# BANK500_501.net
KiCad netlist of a schematic drawn in Altium Designer
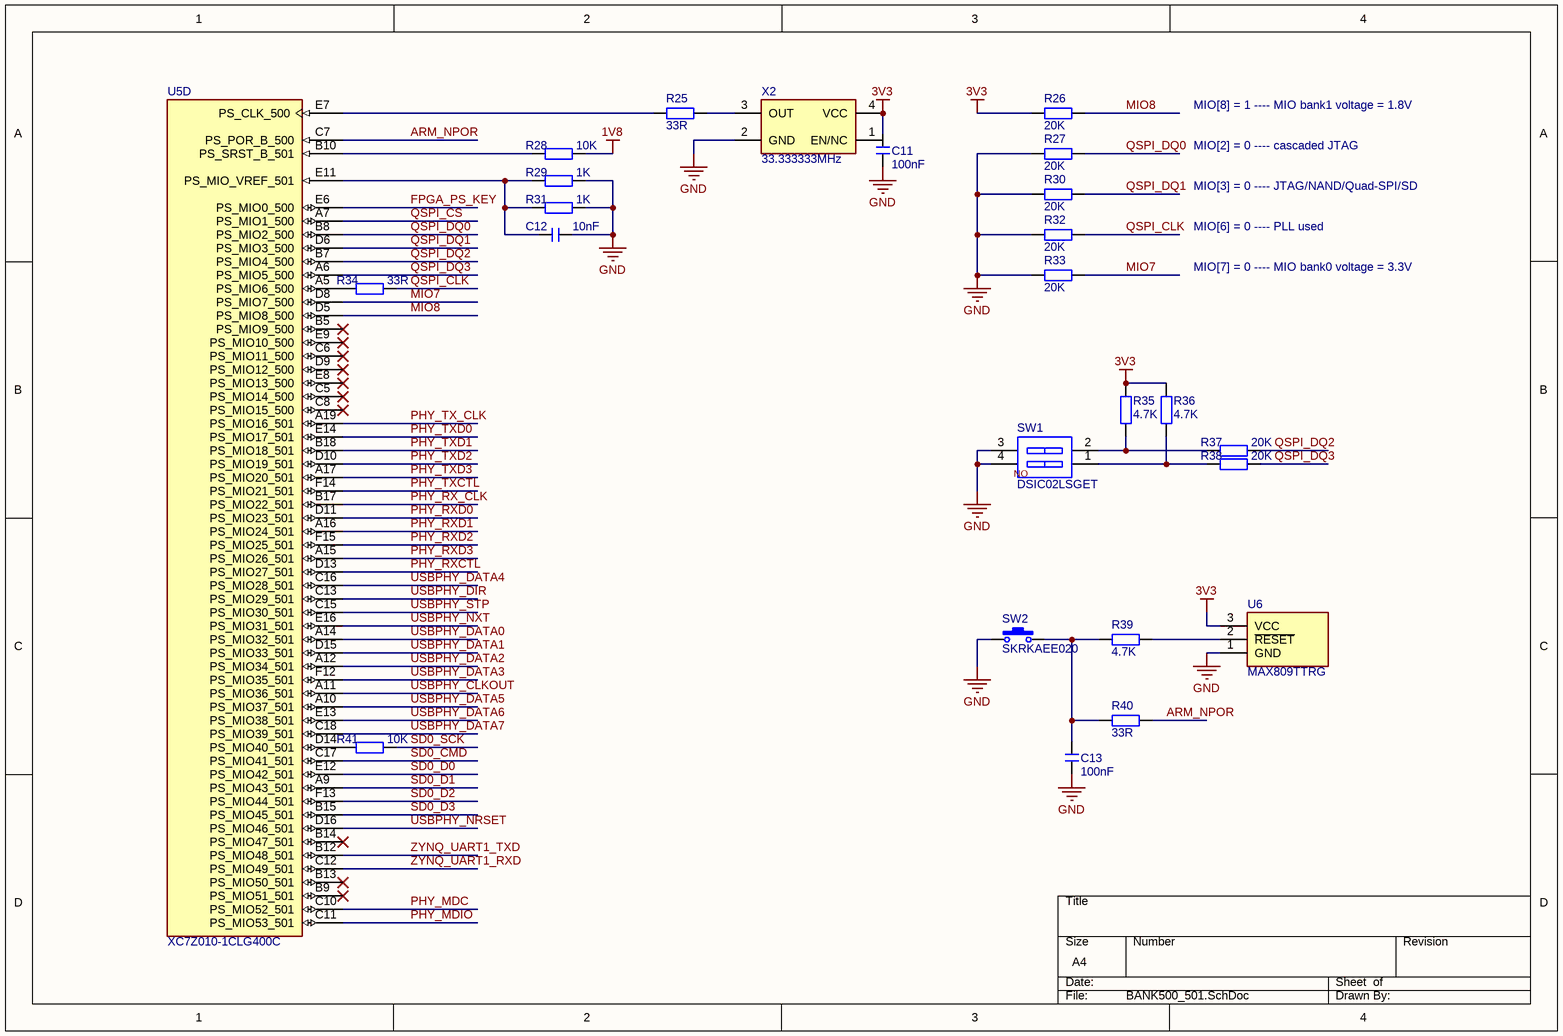
[diagram p0: BANK500_501.SchDoc]

(export (version "E")
  (design (tool "Eeschema 10.0.6"))
  (components
    (comp (ref "C11")
      (value "100nF")
      (footprint "C 0402_L")
      (description "无极性贴片电容")
      (fields (field (name "版权归属") "源创客"))
      (libsource (lib "3.1   - 电阻-电容-电感") (part "C"))
    )
    (comp (ref "C12")
      (value "10nF")
      (footprint "C 0402_L")
      (description "无极性贴片电容")
      (fields (field (name "版权归属") "源创客"))
      (libsource (lib "3.1   - 电阻-电容-电感") (part "C"))
    )
    (comp (ref "C13")
      (value "100nF")
      (footprint "C 0402_L")
      (description "无极性贴片电容")
      (fields (field (name "版权归属") "源创客"))
      (libsource (lib "3.1   - 电阻-电容-电感") (part "C"))
    )
    (comp (ref "R25")
      (value "33R")
      (footprint "R 0805_L")
      (description "贴片电阻")
      (fields (field (name "版权归属") "源创客"))
      (libsource (lib "3.1   - 电阻-电容-电感") (part "R"))
    )
    (comp (ref "R26")
      (value "20K")
      (footprint "R 0805_L")
      (description "贴片电阻")
      (fields (field (name "版权归属") "源创客"))
      (libsource (lib "3.1   - 电阻-电容-电感") (part "R"))
    )
    (comp (ref "R27")
      (value "20K")
      (footprint "R 0805_L")
      (description "贴片电阻")
      (fields (field (name "版权归属") "源创客"))
      (libsource (lib "3.1   - 电阻-电容-电感") (part "R"))
    )
    (comp (ref "R28")
      (value "10K")
      (footprint "R 0402_L")
      (description "贴片电阻")
      (fields (field (name "版权归属") "源创客"))
      (libsource (lib "3.1   - 电阻-电容-电感") (part "R"))
    )
    (comp (ref "R29")
      (value "1K")
      (footprint "R 0402_L")
      (description "贴片电阻")
      (fields (field (name "版权归属") "源创客"))
      (libsource (lib "3.1   - 电阻-电容-电感") (part "R"))
    )
    (comp (ref "R30")
      (value "20K")
      (footprint "R 0805_L")
      (description "贴片电阻")
      (fields (field (name "版权归属") "源创客"))
      (libsource (lib "3.1   - 电阻-电容-电感") (part "R"))
    )
    (comp (ref "R31")
      (value "1K")
      (footprint "R 0402_L")
      (description "贴片电阻")
      (fields (field (name "版权归属") "源创客"))
      (libsource (lib "3.1   - 电阻-电容-电感") (part "R"))
    )
    (comp (ref "R32")
      (value "20K")
      (footprint "R 0805_L")
      (description "贴片电阻")
      (fields (field (name "版权归属") "源创客"))
      (libsource (lib "3.1   - 电阻-电容-电感") (part "R"))
    )
    (comp (ref "R33")
      (value "20K")
      (footprint "R 0805_L")
      (description "贴片电阻")
      (fields (field (name "版权归属") "源创客"))
      (libsource (lib "3.1   - 电阻-电容-电感") (part "R"))
    )
    (comp (ref "R34")
      (value "33R")
      (footprint "R 0805_L")
      (description "贴片电阻")
      (fields (field (name "版权归属") "源创客"))
      (libsource (lib "3.1   - 电阻-电容-电感") (part "R"))
    )
    (comp (ref "R35")
      (value "4.7K")
      (footprint "R 0402_L")
      (description "贴片电阻")
      (fields (field (name "版权归属") "源创客"))
      (libsource (lib "3.1   - 电阻-电容-电感") (part "R"))
    )
    (comp (ref "R36")
      (value "4.7K")
      (footprint "R 0402_L")
      (description "贴片电阻")
      (fields (field (name "版权归属") "源创客"))
      (libsource (lib "3.1   - 电阻-电容-电感") (part "R"))
    )
    (comp (ref "R37")
      (value "20K")
      (footprint "R 0805_L")
      (description "贴片电阻")
      (fields (field (name "版权归属") "源创客"))
      (libsource (lib "3.1   - 电阻-电容-电感") (part "R"))
    )
    (comp (ref "R38")
      (value "20K")
      (footprint "R 0805_L")
      (description "贴片电阻")
      (fields (field (name "版权归属") "源创客"))
      (libsource (lib "3.1   - 电阻-电容-电感") (part "R"))
    )
    (comp (ref "R39")
      (value "4.7K")
      (footprint "R 0402_L")
      (description "贴片电阻")
      (fields (field (name "版权归属") "源创客"))
      (libsource (lib "3.1   - 电阻-电容-电感") (part "R"))
    )
    (comp (ref "R40")
      (value "33R")
      (footprint "R 0805_L")
      (description "贴片电阻")
      (fields (field (name "版权归属") "源创客"))
      (libsource (lib "3.1   - 电阻-电容-电感") (part "R"))
    )
    (comp (ref "R41")
      (value "10K")
      (footprint "R 0402_L")
      (description "贴片电阻")
      (fields (field (name "版权归属") "源创客"))
      (libsource (lib "3.1   - 电阻-电容-电感") (part "R"))
    )
    (comp (ref "SW1")
      (value "DSIC02LSGET")
      (footprint "SOP254P930X445-4N")
      (description "2路拨动开关")
      (libsource (lib "5.1   - 按键-开关") (part "DSIC02LSGET"))
    )
    (comp (ref "SW2")
      (value "SKRKAEE020")
      (footprint "SKRKAEE020")
      (description "2.9x3.9轻触开关")
      (libsource (lib "0.5 - 按键_开关_蜂鸣器_保险丝_电池_测试点_Mark点_铜柱") (part "SKRKAEE020"))
    )
    (comp (ref "U5")
      (value "XC7Z010-1CLG400C")
      (footprint "CLG400")
      (description "ZYNQ7000芯片")
      (libsource (lib "16.2 - Xilinx芯片") (part "XC7Z010-1CLG400C"))
    )
    (comp (ref "U6")
      (value "MAX809TTRG")
      (footprint "SOT23-3L")
      (description "电压检测复位芯片")
      (fields (field (name "MOUSER PART NUMBER") "863-MAX809TTRG"))
      (libsource (lib "1.1   - IC芯片") (part "MAX809TTRG"))
    )
    (comp (ref "X2")
      (value "33.333333MHz")
      (footprint "OSC 1612-4P")
      (description "4脚有源晶振")
      (fields (field (name "版权归属") "源创客"))
      (libsource (lib "10.1 - 保险丝-晶振") (part "XTAL-ACT-4P"))
    )
  )
  (nets
    (net (code "1") (name "/ARM_NPOR") (class "Default")
      (node (ref "R40") (pin "1") (pinfunction "1_1") (pintype "passive"))
      (node (ref "U5") (pin "C7") (pinfunction "PS_POR_B_500_C7") (pintype "input"))
    )
    (net (code "2") (name "/FPGA_PS_KEY") (class "Default")
      (node (ref "U5") (pin "E6") (pinfunction "PS_MIO0_500_E6") (pintype "bidirectional"))
    )
    (net (code "3") (name "/MIO7") (class "Default")
      (node (ref "R33") (pin "1") (pinfunction "1_1") (pintype "passive"))
      (node (ref "U5") (pin "D8") (pinfunction "PS_MIO7_500_D8") (pintype "bidirectional"))
    )
    (net (code "4") (name "/MIO8") (class "Default")
      (node (ref "R26") (pin "1") (pinfunction "1_1") (pintype "passive"))
      (node (ref "U5") (pin "D5") (pinfunction "PS_MIO8_500_D5") (pintype "bidirectional"))
    )
    (net (code "5") (name "/PHY_MDC") (class "Default")
      (node (ref "U5") (pin "C10") (pinfunction "PS_MIO52_501_C10") (pintype "bidirectional"))
    )
    (net (code "6") (name "/PHY_MDIO") (class "Default")
      (node (ref "U5") (pin "C11") (pinfunction "PS_MIO53_501_C11") (pintype "bidirectional"))
    )
    (net (code "7") (name "/PHY_RXCTL") (class "Default")
      (node (ref "U5") (pin "D13") (pinfunction "PS_MIO27_501_D13") (pintype "bidirectional"))
    )
    (net (code "8") (name "/PHY_RXD0") (class "Default")
      (node (ref "U5") (pin "D11") (pinfunction "PS_MIO23_501_D11") (pintype "bidirectional"))
    )
    (net (code "9") (name "/PHY_RXD1") (class "Default")
      (node (ref "U5") (pin "A16") (pinfunction "PS_MIO24_501_A16") (pintype "bidirectional"))
    )
    (net (code "10") (name "/PHY_RXD2") (class "Default")
      (node (ref "U5") (pin "F15") (pinfunction "PS_MIO25_501_F15") (pintype "bidirectional"))
    )
    (net (code "11") (name "/PHY_RXD3") (class "Default")
      (node (ref "U5") (pin "A15") (pinfunction "PS_MIO26_501_A15") (pintype "bidirectional"))
    )
    (net (code "12") (name "/PHY_RX_CLK") (class "Default")
      (node (ref "U5") (pin "B17") (pinfunction "PS_MIO22_501_B17") (pintype "bidirectional"))
    )
    (net (code "13") (name "/PHY_TXCTL") (class "Default")
      (node (ref "U5") (pin "F14") (pinfunction "PS_MIO21_501_F14") (pintype "bidirectional"))
    )
    (net (code "14") (name "/PHY_TXD0") (class "Default")
      (node (ref "U5") (pin "E14") (pinfunction "PS_MIO17_501_E14") (pintype "bidirectional"))
    )
    (net (code "15") (name "/PHY_TXD1") (class "Default")
      (node (ref "U5") (pin "B18") (pinfunction "PS_MIO18_501_B18") (pintype "bidirectional"))
    )
    (net (code "16") (name "/PHY_TXD2") (class "Default")
      (node (ref "U5") (pin "D10") (pinfunction "PS_MIO19_501_D10") (pintype "bidirectional"))
    )
    (net (code "17") (name "/PHY_TXD3") (class "Default")
      (node (ref "U5") (pin "A17") (pinfunction "PS_MIO20_501_A17") (pintype "bidirectional"))
    )
    (net (code "18") (name "/PHY_TX_CLK") (class "Default")
      (node (ref "U5") (pin "A19") (pinfunction "PS_MIO16_501_A19") (pintype "bidirectional"))
    )
    (net (code "19") (name "/QSPI_CLK") (class "Default")
      (node (ref "R32") (pin "1") (pinfunction "1_1") (pintype "passive"))
      (node (ref "R34") (pin "1") (pinfunction "1_1") (pintype "passive"))
    )
    (net (code "20") (name "/QSPI_CS") (class "Default")
      (node (ref "U5") (pin "A7") (pinfunction "PS_MIO1_500_A7") (pintype "bidirectional"))
    )
    (net (code "21") (name "/QSPI_DQ0") (class "Default")
      (node (ref "R27") (pin "1") (pinfunction "1_1") (pintype "passive"))
      (node (ref "U5") (pin "B8") (pinfunction "PS_MIO2_500_B8") (pintype "bidirectional"))
    )
    (net (code "22") (name "/QSPI_DQ1") (class "Default")
      (node (ref "R30") (pin "1") (pinfunction "1_1") (pintype "passive"))
      (node (ref "U5") (pin "D6") (pinfunction "PS_MIO3_500_D6") (pintype "bidirectional"))
    )
    (net (code "23") (name "/QSPI_DQ2") (class "Default")
      (node (ref "R37") (pin "1") (pinfunction "1_1") (pintype "passive"))
      (node (ref "U5") (pin "B7") (pinfunction "PS_MIO4_500_B7") (pintype "bidirectional"))
    )
    (net (code "24") (name "/QSPI_DQ3") (class "Default")
      (node (ref "R38") (pin "1") (pinfunction "1_1") (pintype "passive"))
      (node (ref "U5") (pin "A6") (pinfunction "PS_MIO5_500_A6") (pintype "bidirectional"))
    )
    (net (code "25") (name "/SD0_CMD") (class "Default")
      (node (ref "U5") (pin "C17") (pinfunction "PS_MIO41_501_C17") (pintype "bidirectional"))
    )
    (net (code "26") (name "/SD0_D0") (class "Default")
      (node (ref "U5") (pin "E12") (pinfunction "PS_MIO42_501_E12") (pintype "bidirectional"))
    )
    (net (code "27") (name "/SD0_D1") (class "Default")
      (node (ref "U5") (pin "A9") (pinfunction "PS_MIO43_501_A9") (pintype "bidirectional"))
    )
    (net (code "28") (name "/SD0_D2") (class "Default")
      (node (ref "U5") (pin "F13") (pinfunction "PS_MIO44_501_F13") (pintype "bidirectional"))
    )
    (net (code "29") (name "/SD0_D3") (class "Default")
      (node (ref "U5") (pin "B15") (pinfunction "PS_MIO45_501_B15") (pintype "bidirectional"))
    )
    (net (code "30") (name "/SD0_SCK") (class "Default")
      (node (ref "R41") (pin "1") (pinfunction "1_1") (pintype "passive"))
    )
    (net (code "31") (name "/USBPHY_CLKOUT") (class "Default")
      (node (ref "U5") (pin "A11") (pinfunction "PS_MIO36_501_A11") (pintype "bidirectional"))
    )
    (net (code "32") (name "/USBPHY_DATA0") (class "Default")
      (node (ref "U5") (pin "A14") (pinfunction "PS_MIO32_501_A14") (pintype "bidirectional"))
    )
    (net (code "33") (name "/USBPHY_DATA1") (class "Default")
      (node (ref "U5") (pin "D15") (pinfunction "PS_MIO33_501_D15") (pintype "bidirectional"))
    )
    (net (code "34") (name "/USBPHY_DATA2") (class "Default")
      (node (ref "U5") (pin "A12") (pinfunction "PS_MIO34_501_A12") (pintype "bidirectional"))
    )
    (net (code "35") (name "/USBPHY_DATA3") (class "Default")
      (node (ref "U5") (pin "F12") (pinfunction "PS_MIO35_501_F12") (pintype "bidirectional"))
    )
    (net (code "36") (name "/USBPHY_DATA4") (class "Default")
      (node (ref "U5") (pin "C16") (pinfunction "PS_MIO28_501_C16") (pintype "bidirectional"))
    )
    (net (code "37") (name "/USBPHY_DATA5") (class "Default")
      (node (ref "U5") (pin "A10") (pinfunction "PS_MIO37_501_A10") (pintype "bidirectional"))
    )
    (net (code "38") (name "/USBPHY_DATA6") (class "Default")
      (node (ref "U5") (pin "E13") (pinfunction "PS_MIO38_501_E13") (pintype "bidirectional"))
    )
    (net (code "39") (name "/USBPHY_DATA7") (class "Default")
      (node (ref "U5") (pin "C18") (pinfunction "PS_MIO39_501_C18") (pintype "bidirectional"))
    )
    (net (code "40") (name "/USBPHY_DIR") (class "Default")
      (node (ref "U5") (pin "C13") (pinfunction "PS_MIO29_501_C13") (pintype "bidirectional"))
    )
    (net (code "41") (name "/USBPHY_NRSET") (class "Default")
      (node (ref "U5") (pin "D16") (pinfunction "PS_MIO46_501_D16") (pintype "bidirectional"))
    )
    (net (code "42") (name "/USBPHY_NXT") (class "Default")
      (node (ref "U5") (pin "E16") (pinfunction "PS_MIO31_501_E16") (pintype "bidirectional"))
    )
    (net (code "43") (name "/USBPHY_STP") (class "Default")
      (node (ref "U5") (pin "C15") (pinfunction "PS_MIO30_501_C15") (pintype "bidirectional"))
    )
    (net (code "44") (name "/ZYNQ_UART1_RXD") (class "Default")
      (node (ref "U5") (pin "C12") (pinfunction "PS_MIO49_501_C12") (pintype "bidirectional"))
    )
    (net (code "45") (name "/ZYNQ_UART1_TXD") (class "Default")
      (node (ref "U5") (pin "B12") (pinfunction "PS_MIO48_501_B12") (pintype "bidirectional"))
    )
    (net (code "46") (name "1V8") (class "Default")
      (node (ref "R28") (pin "1") (pinfunction "1_1") (pintype "passive"))
    )
    (net (code "47") (name "3V3") (class "Default")
      (node (ref "C11") (pin "2") (pinfunction "2_2") (pintype "passive"))
      (node (ref "R26") (pin "2") (pinfunction "2_2") (pintype "passive"))
      (node (ref "R35") (pin "1") (pinfunction "1_1") (pintype "passive"))
      (node (ref "R36") (pin "1") (pinfunction "1_1") (pintype "passive"))
      (node (ref "U6") (pin "3") (pinfunction "VCC_3") (pintype "power_in"))
      (node (ref "X2") (pin "4") (pinfunction "VCC_4") (pintype "passive"))
    )
    (net (code "48") (name "GND") (class "Default")
      (node (ref "C11") (pin "1") (pinfunction "1_1") (pintype "passive"))
      (node (ref "C12") (pin "1") (pinfunction "1_1") (pintype "passive"))
      (node (ref "C13") (pin "1") (pinfunction "1_1") (pintype "passive"))
      (node (ref "R27") (pin "2") (pinfunction "2_2") (pintype "passive"))
      (node (ref "R29") (pin "1") (pinfunction "1_1") (pintype "passive"))
      (node (ref "R30") (pin "2") (pinfunction "2_2") (pintype "passive"))
      (node (ref "R31") (pin "1") (pinfunction "1_1") (pintype "passive"))
      (node (ref "R32") (pin "2") (pinfunction "2_2") (pintype "passive"))
      (node (ref "R33") (pin "2") (pinfunction "2_2") (pintype "passive"))
      (node (ref "SW1") (pin "3") (pinfunction "3_3") (pintype "passive"))
      (node (ref "SW1") (pin "4") (pinfunction "4_4") (pintype "passive"))
      (node (ref "SW2") (pin "1") (pinfunction "1_1") (pintype "passive"))
      (node (ref "U6") (pin "1") (pinfunction "GND_1") (pintype "power_in"))
      (node (ref "X2") (pin "2") (pinfunction "GND_2") (pintype "passive"))
    )
    (net (code "49") (name "Net-(C13-Pad2)") (class "Default")
      (node (ref "C13") (pin "2") (pinfunction "2_2") (pintype "passive"))
      (node (ref "R39") (pin "2") (pinfunction "2_2") (pintype "passive"))
      (node (ref "R40") (pin "2") (pinfunction "2_2") (pintype "passive"))
      (node (ref "SW2") (pin "2") (pinfunction "2_2") (pintype "passive"))
    )
    (net (code "50") (name "Net-(R35-Pad2)") (class "Default")
      (node (ref "R35") (pin "2") (pinfunction "2_2") (pintype "passive"))
      (node (ref "R37") (pin "2") (pinfunction "2_2") (pintype "passive"))
      (node (ref "SW1") (pin "2") (pinfunction "2_2") (pintype "passive"))
    )
    (net (code "51") (name "Net-(R36-Pad2)") (class "Default")
      (node (ref "R36") (pin "2") (pinfunction "2_2") (pintype "passive"))
      (node (ref "R38") (pin "2") (pinfunction "2_2") (pintype "passive"))
      (node (ref "SW1") (pin "1") (pinfunction "1_1") (pintype "passive"))
    )
    (net (code "52") (name "Net-(U5D-PS_CLK_500)") (class "Default")
      (node (ref "R25") (pin "2") (pinfunction "2_2") (pintype "passive"))
      (node (ref "U5") (pin "E7") (pinfunction "PS_CLK_500_E7") (pintype "input"))
    )
    (net (code "53") (name "Net-(U5D-PS_MIO6_500)") (class "Default")
      (node (ref "R34") (pin "2") (pinfunction "2_2") (pintype "passive"))
      (node (ref "U5") (pin "A5") (pinfunction "PS_MIO6_500_A5") (pintype "bidirectional"))
    )
    (net (code "54") (name "Net-(U5D-PS_MIO40_501)") (class "Default")
      (node (ref "R41") (pin "2") (pinfunction "2_2") (pintype "passive"))
      (node (ref "U5") (pin "D14") (pinfunction "PS_MIO40_501_D14") (pintype "bidirectional"))
    )
    (net (code "55") (name "Net-(U5D-PS_MIO_VREF_501)") (class "Default")
      (node (ref "C12") (pin "2") (pinfunction "2_2") (pintype "passive"))
      (node (ref "R29") (pin "2") (pinfunction "2_2") (pintype "passive"))
      (node (ref "R31") (pin "2") (pinfunction "2_2") (pintype "passive"))
      (node (ref "U5") (pin "E11") (pinfunction "PS_MIO_VREF_501_E11") (pintype "input"))
    )
    (net (code "56") (name "Net-(U5D-PS_SRST_B_501)") (class "Default")
      (node (ref "R28") (pin "2") (pinfunction "2_2") (pintype "passive"))
      (node (ref "U5") (pin "B10") (pinfunction "PS_SRST_B_501_B10") (pintype "input"))
    )
    (net (code "57") (name "Net-(U6-~{RESET})") (class "Default")
      (node (ref "R39") (pin "1") (pinfunction "1_1") (pintype "passive"))
      (node (ref "U6") (pin "2") (pinfunction "~{RESET}_2") (pintype "passive"))
    )
    (net (code "58") (name "Net-(X2-OUT)") (class "Default")
      (node (ref "R25") (pin "1") (pinfunction "1_1") (pintype "passive"))
      (node (ref "X2") (pin "3") (pinfunction "OUT_3") (pintype "passive"))
    )
    (net (code "59") (name "unconnected-(U5D-PS_MIO9_500-PadB5)") (class "Default")
      (node (ref "U5") (pin "B5") (pinfunction "PS_MIO9_500_B5") (pintype "bidirectional+no_connect"))
    )
    (net (code "60") (name "unconnected-(U5D-PS_MIO10_500-PadE9)") (class "Default")
      (node (ref "U5") (pin "E9") (pinfunction "PS_MIO10_500_E9") (pintype "bidirectional+no_connect"))
    )
    (net (code "61") (name "unconnected-(U5D-PS_MIO11_500-PadC6)") (class "Default")
      (node (ref "U5") (pin "C6") (pinfunction "PS_MIO11_500_C6") (pintype "bidirectional+no_connect"))
    )
    (net (code "62") (name "unconnected-(U5D-PS_MIO12_500-PadD9)") (class "Default")
      (node (ref "U5") (pin "D9") (pinfunction "PS_MIO12_500_D9") (pintype "bidirectional+no_connect"))
    )
    (net (code "63") (name "unconnected-(U5D-PS_MIO13_500-PadE8)") (class "Default")
      (node (ref "U5") (pin "E8") (pinfunction "PS_MIO13_500_E8") (pintype "bidirectional+no_connect"))
    )
    (net (code "64") (name "unconnected-(U5D-PS_MIO14_500-PadC5)") (class "Default")
      (node (ref "U5") (pin "C5") (pinfunction "PS_MIO14_500_C5") (pintype "bidirectional+no_connect"))
    )
    (net (code "65") (name "unconnected-(U5D-PS_MIO15_500-PadC8)") (class "Default")
      (node (ref "U5") (pin "C8") (pinfunction "PS_MIO15_500_C8") (pintype "bidirectional+no_connect"))
    )
    (net (code "66") (name "unconnected-(U5D-PS_MIO47_501-PadB14)") (class "Default")
      (node (ref "U5") (pin "B14") (pinfunction "PS_MIO47_501_B14") (pintype "bidirectional+no_connect"))
    )
    (net (code "67") (name "unconnected-(U5D-PS_MIO50_501-PadB13)") (class "Default")
      (node (ref "U5") (pin "B13") (pinfunction "PS_MIO50_501_B13") (pintype "bidirectional+no_connect"))
    )
    (net (code "68") (name "unconnected-(U5D-PS_MIO51_501-PadB9)") (class "Default")
      (node (ref "U5") (pin "B9") (pinfunction "PS_MIO51_501_B9") (pintype "bidirectional+no_connect"))
    )
    (net (code "69") (name "unconnected-(X2-EN{slash}NC-Pad1)") (class "Default")
      (node (ref "X2") (pin "1") (pinfunction "EN/NC_1") (pintype "passive"))
    )
  )
)
